# schematic.net
KiCad netlist of a schematic drawn in Altium Designer
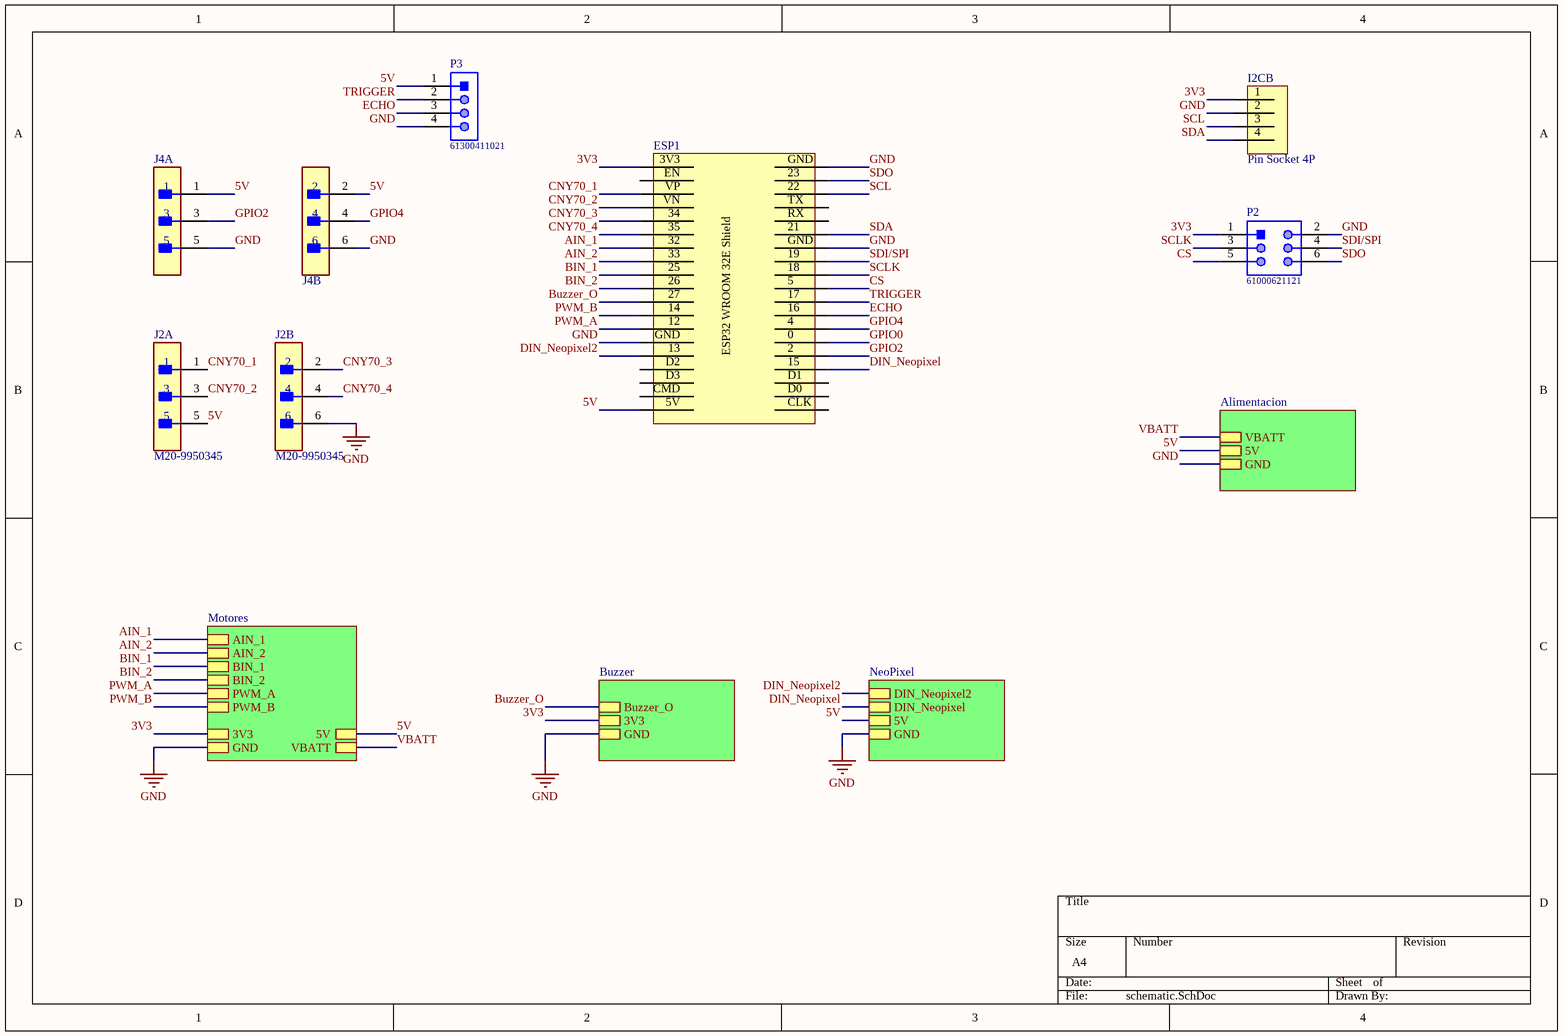
[diagram p0: schematic.SchDoc]

(export (version "E")
  (design (tool "Eeschema 10.0.6"))
  (components
    (comp (ref "ESP1")
      (value "Shield_ESP32_WR32E")
      (footprint "Shield_ESP32_WR32E")
      (libsource (lib "Isidro_Library") (part "Shield_ESP32_WR32E"))
    )
    (comp (ref "I2C")
      (value "Pin Socket 4P")
      (footprint "Pin Socket 4P")
      (description "Female Header 4 1 Straight，180degrees 2.54mm Through Hole,P=2.54mm Pin Header & Female Header RoHS")
      (libsource (lib "Isidro_Library") (part "Pin Socket 4P"))
    )
    (comp (ref "J2")
      (value "M20-9950345")
      (footprint "FP-M20-9950345-MFG")
      (description "CONN HEADER R/A 6POS 2.54MM")
      (fields
        (field (name "OCTOPART") "https://octopart.com/m20-9950345-harwin-21265213")
        (field (name "MANUFACTURER") "Harwin")
      )
      (libsource (lib "Altium Content Vault") (part "b76336891f9c52daa0497ceff74f613"))
    )
    (comp (ref "J4")
      (value "M20-9950345")
      (footprint "FP-M20-9950345-MFG")
      (description "CONN HEADER R/A 6POS 2.54MM")
      (fields
        (field (name "OCTOPART") "https://octopart.com/m20-9950345-harwin-21265213")
        (field (name "MANUFACTURER") "Harwin")
      )
      (libsource (lib "Altium Content Vault") (part "b76336891f9c52daa0497ceff74f613"))
    )
    (comp (ref "P2")
      (value "61000621121")
      (footprint "61000621121")
      (description "SMT Vertical Pin Header WR-PHD, Pitch 2.54 mm, Dual Row, 6 pins")
      (fields (field (name "MANUFACTURER") "Wurth Elektronik") (field (name "PUBLISHER") "WurthElektronik"))
      (libsource (lib "Altium Content Vault") (part "WE-CN-2P-M-R6"))
    )
    (comp (ref "P3")
      (value "61300411021")
      (footprint "61300411021")
      (description "THT Angled Pin Header WR-PHD, Pitch 2.54 mm, Single Row, 4 pins")
      (fields (field (name "MANUFACTURER") "Wurth Elektronik") (field (name "PUBLISHER") "WurthElektronik"))
      (libsource (lib "Altium Content Vault") (part "WE-CN-1P-M-R4"))
    )
  )
  (nets
    (net (code "1") (name "/3V3") (class "Default")
      (node (ref "ESP1") (pin "3V3") (pinfunction "3V3_3V3") (pintype "passive"))
      (node (ref "I2C") (pin "1") (pinfunction "1_1") (pintype "passive"))
      (node (ref "P2") (pin "1") (pinfunction "1_1") (pintype "passive"))
    )
    (net (code "2") (name "/5V") (class "Default")
      (node (ref "ESP1") (pin "5V") (pinfunction "5V_5V") (pintype "passive"))
      (node (ref "J2") (pin "5") (pinfunction "5_5") (pintype "passive"))
      (node (ref "J4") (pin "1") (pinfunction "1_1") (pintype "passive"))
      (node (ref "J4") (pin "2") (pinfunction "2_2") (pintype "passive"))
      (node (ref "P3") (pin "1") (pinfunction "1_1") (pintype "passive"))
    )
    (net (code "3") (name "/AIN_1") (class "Default")
      (node (ref "ESP1") (pin "32") (pinfunction "32_32") (pintype "passive"))
    )
    (net (code "4") (name "/AIN_2") (class "Default")
      (node (ref "ESP1") (pin "33") (pinfunction "33_33") (pintype "passive"))
    )
    (net (code "5") (name "/BIN_1") (class "Default")
      (node (ref "ESP1") (pin "25") (pinfunction "25_25") (pintype "passive"))
    )
    (net (code "6") (name "/BIN_2") (class "Default")
      (node (ref "ESP1") (pin "26") (pinfunction "26_26") (pintype "passive"))
    )
    (net (code "7") (name "/Buzzer_O") (class "Default")
      (node (ref "ESP1") (pin "27") (pinfunction "27_27") (pintype "passive"))
    )
    (net (code "8") (name "/CNY70_1") (class "Default")
      (node (ref "ESP1") (pin "VP") (pinfunction "VP_VP") (pintype "passive"))
      (node (ref "J2") (pin "1") (pinfunction "1_1") (pintype "passive"))
    )
    (net (code "9") (name "/CNY70_2") (class "Default")
      (node (ref "ESP1") (pin "VN") (pinfunction "VN_VN") (pintype "passive"))
      (node (ref "J2") (pin "3") (pinfunction "3_3") (pintype "passive"))
    )
    (net (code "10") (name "/CNY70_3") (class "Default")
      (node (ref "ESP1") (pin "34") (pinfunction "34_34") (pintype "passive"))
      (node (ref "J2") (pin "2") (pinfunction "2_2") (pintype "passive"))
    )
    (net (code "11") (name "/CNY70_4") (class "Default")
      (node (ref "ESP1") (pin "35") (pinfunction "35_35") (pintype "passive"))
      (node (ref "J2") (pin "4") (pinfunction "4_4") (pintype "passive"))
    )
    (net (code "12") (name "/CS") (class "Default")
      (node (ref "ESP1") (pin "5") (pinfunction "5_5") (pintype "passive"))
      (node (ref "P2") (pin "5") (pinfunction "5_5") (pintype "passive"))
    )
    (net (code "13") (name "/DIN_Neopixel") (class "Default")
      (node (ref "ESP1") (pin "15") (pinfunction "15_15") (pintype "passive"))
    )
    (net (code "14") (name "/DIN_Neopixel2") (class "Default")
      (node (ref "ESP1") (pin "13") (pinfunction "13_13") (pintype "passive"))
    )
    (net (code "15") (name "/ECHO") (class "Default")
      (node (ref "ESP1") (pin "16") (pinfunction "16_16") (pintype "passive"))
      (node (ref "P3") (pin "3") (pinfunction "3_3") (pintype "passive"))
    )
    (net (code "16") (name "/GPIO0") (class "Default")
      (node (ref "ESP1") (pin "0") (pinfunction "0_0") (pintype "passive"))
    )
    (net (code "17") (name "/GPIO2") (class "Default")
      (node (ref "ESP1") (pin "2") (pinfunction "2_2") (pintype "passive"))
      (node (ref "J4") (pin "3") (pinfunction "3_3") (pintype "passive"))
    )
    (net (code "18") (name "/GPIO4") (class "Default")
      (node (ref "ESP1") (pin "4") (pinfunction "4_4") (pintype "passive"))
      (node (ref "J4") (pin "4") (pinfunction "4_4") (pintype "passive"))
    )
    (net (code "19") (name "/PWM_A") (class "Default")
      (node (ref "ESP1") (pin "12") (pinfunction "12_12") (pintype "passive"))
    )
    (net (code "20") (name "/PWM_B") (class "Default")
      (node (ref "ESP1") (pin "14") (pinfunction "14_14") (pintype "passive"))
    )
    (net (code "21") (name "/SCL") (class "Default")
      (node (ref "ESP1") (pin "22") (pinfunction "22_22") (pintype "passive"))
      (node (ref "I2C") (pin "3") (pinfunction "3_3") (pintype "passive"))
    )
    (net (code "22") (name "/SCLK") (class "Default")
      (node (ref "ESP1") (pin "18") (pinfunction "18_18") (pintype "passive"))
      (node (ref "P2") (pin "3") (pinfunction "3_3") (pintype "passive"))
    )
    (net (code "23") (name "/SDA") (class "Default")
      (node (ref "ESP1") (pin "21") (pinfunction "21_21") (pintype "passive"))
      (node (ref "I2C") (pin "4") (pinfunction "4_4") (pintype "passive"))
    )
    (net (code "24") (name "/SDI{slash}SPI") (class "Default")
      (node (ref "ESP1") (pin "19") (pinfunction "19_19") (pintype "passive"))
      (node (ref "P2") (pin "4") (pinfunction "4_4") (pintype "passive"))
    )
    (net (code "25") (name "/SDO") (class "Default")
      (node (ref "ESP1") (pin "23") (pinfunction "23_23") (pintype "passive"))
      (node (ref "P2") (pin "6") (pinfunction "6_6") (pintype "passive"))
    )
    (net (code "26") (name "/TRIGGER") (class "Default")
      (node (ref "ESP1") (pin "17") (pinfunction "17_17") (pintype "passive"))
      (node (ref "P3") (pin "2") (pinfunction "2_2") (pintype "passive"))
    )
    (net (code "28") (name "GND") (class "Default")
      (node (ref "ESP1") (pin "GND") (pinfunction "GND_GND") (pintype "passive"))
      (node (ref "I2C") (pin "2") (pinfunction "2_2") (pintype "passive"))
      (node (ref "J2") (pin "6") (pinfunction "6_6") (pintype "passive"))
      (node (ref "J4") (pin "5") (pinfunction "5_5") (pintype "passive"))
      (node (ref "J4") (pin "6") (pinfunction "6_6") (pintype "passive"))
      (node (ref "P2") (pin "2") (pinfunction "2_2") (pintype "passive"))
      (node (ref "P3") (pin "4") (pinfunction "4_4") (pintype "passive"))
    )
    (net (code "29") (name "unconnected-(ESP1-PadCLK)") (class "Default")
      (node (ref "ESP1") (pin "CLK") (pinfunction "CLK_CLK") (pintype "passive"))
    )
    (net (code "30") (name "unconnected-(ESP1-PadCMD)") (class "Default")
      (node (ref "ESP1") (pin "CMD") (pinfunction "CMD_CMD") (pintype "passive"))
    )
    (net (code "31") (name "unconnected-(ESP1-PadD0)") (class "Default")
      (node (ref "ESP1") (pin "D0") (pinfunction "D0_D0") (pintype "passive"))
    )
    (net (code "32") (name "unconnected-(ESP1-PadD1)") (class "Default")
      (node (ref "ESP1") (pin "D1") (pinfunction "D1_D1") (pintype "passive"))
    )
    (net (code "33") (name "unconnected-(ESP1-PadD2)") (class "Default")
      (node (ref "ESP1") (pin "D2") (pinfunction "D2_D2") (pintype "passive"))
    )
    (net (code "34") (name "unconnected-(ESP1-PadD3)") (class "Default")
      (node (ref "ESP1") (pin "D3") (pinfunction "D3_D3") (pintype "passive"))
    )
    (net (code "35") (name "unconnected-(ESP1-PadEN)") (class "Default")
      (node (ref "ESP1") (pin "EN") (pinfunction "EN_EN") (pintype "passive"))
    )
    (net (code "36") (name "unconnected-(ESP1-PadRX)") (class "Default")
      (node (ref "ESP1") (pin "RX") (pinfunction "RX_RX") (pintype "passive"))
    )
    (net (code "37") (name "unconnected-(ESP1-PadTX)") (class "Default")
      (node (ref "ESP1") (pin "TX") (pinfunction "TX_TX") (pintype "passive"))
    )
  )
)
